# 0.net
KiCad netlist of a schematic drawn in Altium Designer
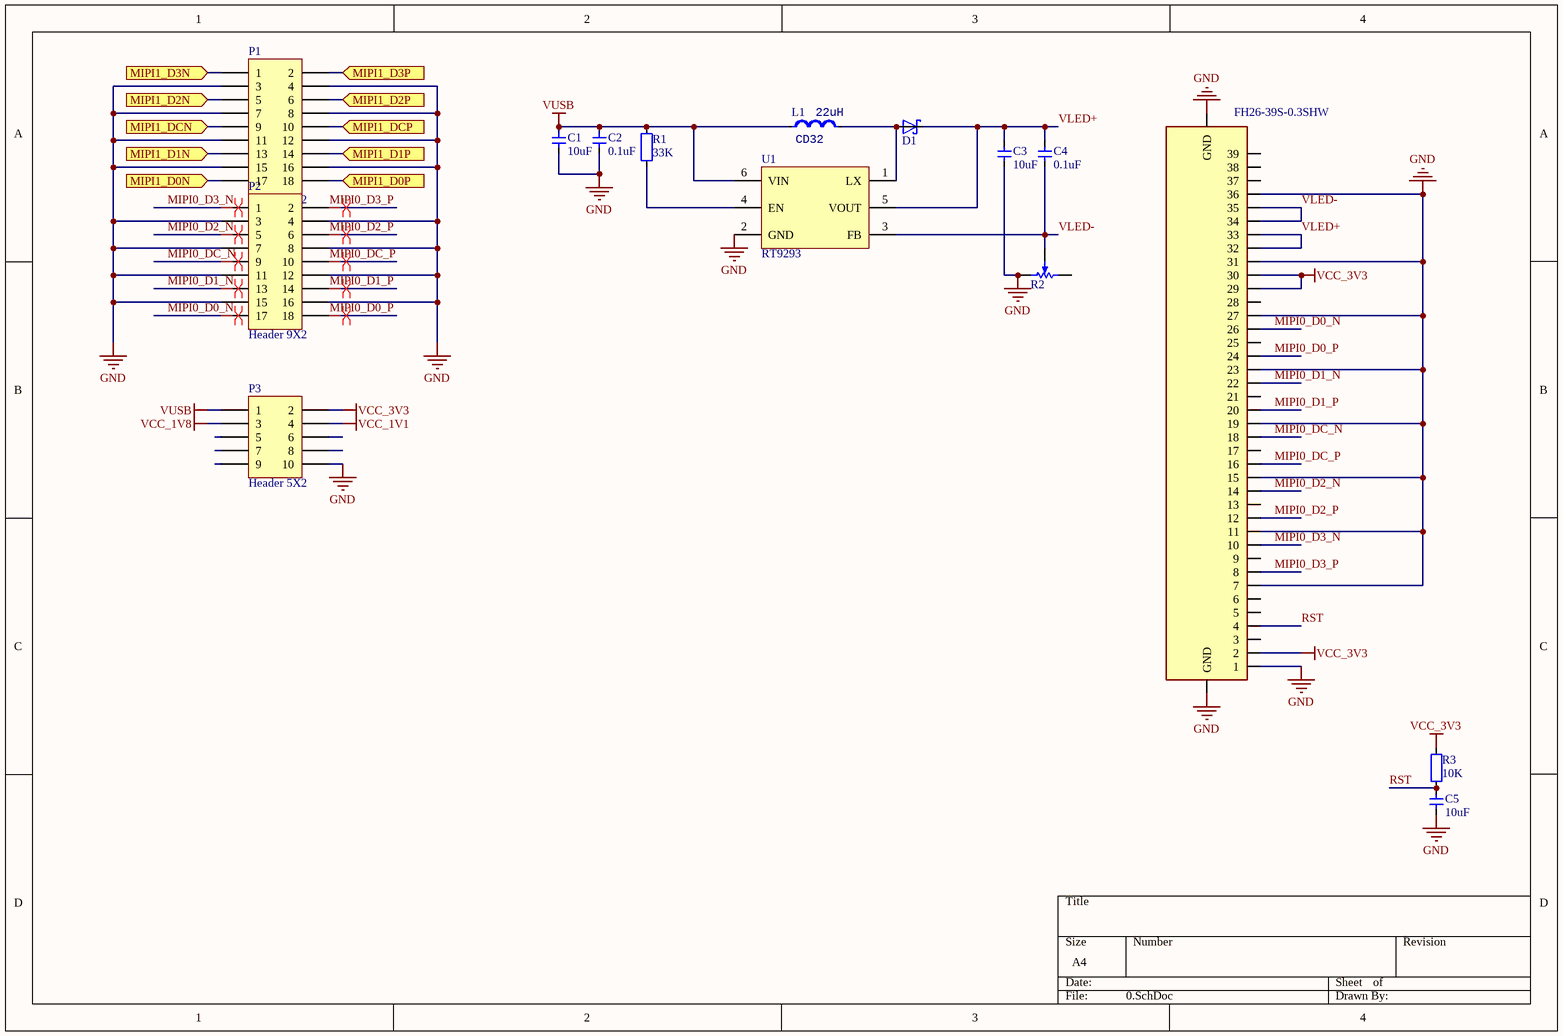
[diagram p0: 0.SchDoc]

(export (version "E")
  (design (tool "Eeschema 10.0.6"))
  (components
    (comp (ref "1")
      (value "FH26-39S-0.3SHW")
      (footprint "FH26-39S-0.3SHW")
      (description "39 Position FPC Connector Contacts, Bottom 0.012 _0.30mm_ Surface Mount, Right Angle")
      (fields (field (name "MF") "Hirose"))
      (libsource (lib "mLib") (part "FH26-39S-0.3SHW"))
    )
    (comp (ref "C1")
      (value "10uF")
      (footprint "0603_CAP")
      (description "Capacitor")
      (libsource (lib "MyPcbLib") (part "电容-0402"))
    )
    (comp (ref "C2")
      (value "0.1uF")
      (footprint "0603_CAP")
      (description "Capacitor")
      (libsource (lib "MyPcbLib") (part "电容-0402"))
    )
    (comp (ref "C3")
      (value "10uF")
      (footprint "0603_CAP")
      (description "Capacitor")
      (libsource (lib "MyPcbLib") (part "电容-0402"))
    )
    (comp (ref "C4")
      (value "0.1uF")
      (footprint "0603_CAP")
      (description "Capacitor")
      (libsource (lib "MyPcbLib") (part "电容-0402"))
    )
    (comp (ref "C5")
      (value "10uF")
      (footprint "0603_CAP")
      (description "Capacitor")
      (libsource (lib "MyPcbLib") (part "电容-0402"))
    )
    (comp (ref "D1")
      (value "RSX501L-20")
      (footprint "SOD-123F_L2.8-W1.8-LS3.7-RD")
      (description "Diode Schottky 40V 1A Surface Mount SMA _DO-214AC_")
      (fields (field (name "MP") "SS14") (field (name "MF") "ON Semiconductor"))
      (libsource (lib "mLib") (part "RSX501L-20"))
    )
    (comp (ref "L1")
      (value "22uH")
      (footprint "IND_CD32")
      (description "Inductor")
      (fields (field (name "TYPE") "CD32") (field (name "Comment") "CD32"))
      (libsource (lib "KitSprout") (part "Ind_CD32"))
    )
    (comp (ref "P1")
      (value "Header 9X2")
      (footprint "HDR2X9")
      (description "Header, 9-Pin, Dual row")
      (fields (field (name "PUBLISHER") "Altium Limited"))
      (libsource (lib "Miscellaneous Connectors") (part "Header 9X2"))
    )
    (comp (ref "P2")
      (value "Header 9X2")
      (footprint "HDR2X9")
      (description "Header, 9-Pin, Dual row")
      (fields (field (name "PUBLISHER") "Altium Limited"))
      (libsource (lib "Miscellaneous Connectors") (part "Header 9X2"))
    )
    (comp (ref "P3")
      (value "Header 5X2")
      (footprint "HDR2X5")
      (description "Header, 5-Pin, Dual row")
      (fields (field (name "PUBLISHER") "Altium Limited"))
      (libsource (lib "Miscellaneous Connectors") (part "Header 5X2"))
    )
    (comp (ref "R1")
      (value "33K")
      (footprint "0603_RES")
      (description "Resistor")
      (libsource (lib "MyPcbLib") (part "电阻-0402"))
    )
    (comp (ref "R2")
      (value "电位器-贴片")
      (footprint "贴片电位器 3*3")
      (fields (field (name "PUBLISHER") "Altium Limited"))
      (libsource (lib "MyPcbLib") (part "电位器-贴片"))
    )
    (comp (ref "R3")
      (value "10K")
      (footprint "0603_RES")
      (description "Resistor")
      (libsource (lib "MyPcbLib") (part "电阻-0402"))
    )
    (comp (ref "U1")
      (value "RT9293")
      (footprint "SOT23-6")
      (description "LCD-LED Driver")
      (libsource (lib "mLib") (part "RT9293"))
    )
  )
  (nets
    (net (code "1") (name "/MIPI0_D0_N") (class "Default")
      (node (ref "1") (pin "26") (pinfunction "26_26") (pintype "bidirectional"))
      (node (ref "P2") (pin "17") (pinfunction "17_17") (pintype "passive"))
    )
    (net (code "2") (name "/MIPI0_D0_P") (class "Default")
      (node (ref "1") (pin "24") (pinfunction "24_24") (pintype "bidirectional"))
      (node (ref "P2") (pin "18") (pinfunction "18_18") (pintype "passive"))
    )
    (net (code "3") (name "/MIPI0_D1_N") (class "Default")
      (node (ref "1") (pin "22") (pinfunction "22_22") (pintype "bidirectional"))
      (node (ref "P2") (pin "13") (pinfunction "13_13") (pintype "passive"))
    )
    (net (code "4") (name "/MIPI0_D1_P") (class "Default")
      (node (ref "1") (pin "20") (pinfunction "20_20") (pintype "bidirectional"))
      (node (ref "P2") (pin "14") (pinfunction "14_14") (pintype "passive"))
    )
    (net (code "5") (name "/MIPI0_D2_N") (class "Default")
      (node (ref "1") (pin "14") (pinfunction "14_14") (pintype "bidirectional"))
      (node (ref "P2") (pin "5") (pinfunction "5_5") (pintype "passive"))
    )
    (net (code "6") (name "/MIPI0_D2_P") (class "Default")
      (node (ref "1") (pin "12") (pinfunction "12_12") (pintype "bidirectional"))
      (node (ref "P2") (pin "6") (pinfunction "6_6") (pintype "passive"))
    )
    (net (code "7") (name "/MIPI0_D3_N") (class "Default")
      (node (ref "1") (pin "10") (pinfunction "10_10") (pintype "bidirectional"))
      (node (ref "P2") (pin "1") (pinfunction "1_1") (pintype "passive"))
    )
    (net (code "8") (name "/MIPI0_D3_P") (class "Default")
      (node (ref "1") (pin "8") (pinfunction "8_8") (pintype "bidirectional"))
      (node (ref "P2") (pin "2") (pinfunction "2_2") (pintype "passive"))
    )
    (net (code "9") (name "/MIPI0_DC_N") (class "Default")
      (node (ref "1") (pin "18") (pinfunction "18_18") (pintype "bidirectional"))
      (node (ref "P2") (pin "9") (pinfunction "9_9") (pintype "passive"))
    )
    (net (code "10") (name "/MIPI0_DC_P") (class "Default")
      (node (ref "1") (pin "16") (pinfunction "16_16") (pintype "bidirectional"))
      (node (ref "P2") (pin "10") (pinfunction "10_10") (pintype "passive"))
    )
    (net (code "11") (name "/MIPI1_D0N") (class "Default")
      (node (ref "P1") (pin "17") (pinfunction "17_17") (pintype "passive"))
    )
    (net (code "12") (name "/MIPI1_D0P") (class "Default")
      (node (ref "P1") (pin "18") (pinfunction "18_18") (pintype "passive"))
    )
    (net (code "13") (name "/MIPI1_D1N") (class "Default")
      (node (ref "P1") (pin "13") (pinfunction "13_13") (pintype "passive"))
    )
    (net (code "14") (name "/MIPI1_D1P") (class "Default")
      (node (ref "P1") (pin "14") (pinfunction "14_14") (pintype "passive"))
    )
    (net (code "15") (name "/MIPI1_D2N") (class "Default")
      (node (ref "P1") (pin "5") (pinfunction "5_5") (pintype "passive"))
    )
    (net (code "16") (name "/MIPI1_D2P") (class "Default")
      (node (ref "P1") (pin "6") (pinfunction "6_6") (pintype "passive"))
    )
    (net (code "17") (name "/MIPI1_D3N") (class "Default")
      (node (ref "P1") (pin "1") (pinfunction "1_1") (pintype "passive"))
    )
    (net (code "18") (name "/MIPI1_D3P") (class "Default")
      (node (ref "P1") (pin "2") (pinfunction "2_2") (pintype "passive"))
    )
    (net (code "19") (name "/MIPI1_DCN") (class "Default")
      (node (ref "P1") (pin "9") (pinfunction "9_9") (pintype "passive"))
    )
    (net (code "20") (name "/MIPI1_DCP") (class "Default")
      (node (ref "P1") (pin "10") (pinfunction "10_10") (pintype "passive"))
    )
    (net (code "21") (name "/RST") (class "Default")
      (node (ref "1") (pin "4") (pinfunction "4_4") (pintype "bidirectional"))
      (node (ref "C5") (pin "2") (pinfunction "2_2") (pintype "passive"))
      (node (ref "R3") (pin "1") (pinfunction "1_1") (pintype "passive"))
    )
    (net (code "22") (name "/VLED+") (class "Default")
      (node (ref "1") (pin "32") (pinfunction "32_32") (pintype "bidirectional"))
      (node (ref "1") (pin "33") (pinfunction "33_33") (pintype "bidirectional"))
      (node (ref "C3") (pin "2") (pinfunction "2_2") (pintype "passive"))
      (node (ref "C4") (pin "2") (pinfunction "2_2") (pintype "passive"))
      (node (ref "D1") (pin "1") (pinfunction "1_1") (pintype "passive"))
      (node (ref "U1") (pin "5") (pinfunction "VOUT_5") (pintype "passive"))
    )
    (net (code "23") (name "/VLED-") (class "Default")
      (node (ref "1") (pin "34") (pinfunction "34_34") (pintype "bidirectional"))
      (node (ref "1") (pin "35") (pinfunction "35_35") (pintype "bidirectional"))
      (node (ref "C4") (pin "1") (pinfunction "1_1") (pintype "passive"))
      (node (ref "R2") (pin "3") (pinfunction "W_3") (pintype "passive"))
      (node (ref "U1") (pin "3") (pinfunction "FB_3") (pintype "passive"))
    )
    (net (code "24") (name "GND") (class "Default")
      (node (ref "1") (pin "1") (pinfunction "1_1") (pintype "bidirectional"))
      (node (ref "1") (pin "11") (pinfunction "11_11") (pintype "bidirectional"))
      (node (ref "1") (pin "15") (pinfunction "15_15") (pintype "bidirectional"))
      (node (ref "1") (pin "19") (pinfunction "19_19") (pintype "bidirectional"))
      (node (ref "1") (pin "23") (pinfunction "23_23") (pintype "bidirectional"))
      (node (ref "1") (pin "27") (pinfunction "27_27") (pintype "bidirectional"))
      (node (ref "1") (pin "31") (pinfunction "31_31") (pintype "bidirectional"))
      (node (ref "1") (pin "36") (pinfunction "36_36") (pintype "bidirectional"))
      (node (ref "1") (pin "7") (pinfunction "7_7") (pintype "bidirectional"))
      (node (ref "1") (pin "GND1") (pinfunction "GND_GND1") (pintype "power_in"))
      (node (ref "1") (pin "GND2") (pinfunction "GND_GND2") (pintype "power_in"))
      (node (ref "C1") (pin "1") (pinfunction "1_1") (pintype "passive"))
      (node (ref "C2") (pin "1") (pinfunction "1_1") (pintype "passive"))
      (node (ref "C3") (pin "1") (pinfunction "1_1") (pintype "passive"))
      (node (ref "C5") (pin "1") (pinfunction "1_1") (pintype "passive"))
      (node (ref "P1") (pin "11") (pinfunction "11_11") (pintype "passive"))
      (node (ref "P1") (pin "12") (pinfunction "12_12") (pintype "passive"))
      (node (ref "P1") (pin "15") (pinfunction "15_15") (pintype "passive"))
      (node (ref "P1") (pin "16") (pinfunction "16_16") (pintype "passive"))
      (node (ref "P1") (pin "3") (pinfunction "3_3") (pintype "passive"))
      (node (ref "P1") (pin "4") (pinfunction "4_4") (pintype "passive"))
      (node (ref "P1") (pin "7") (pinfunction "7_7") (pintype "passive"))
      (node (ref "P1") (pin "8") (pinfunction "8_8") (pintype "passive"))
      (node (ref "P2") (pin "11") (pinfunction "11_11") (pintype "passive"))
      (node (ref "P2") (pin "12") (pinfunction "12_12") (pintype "passive"))
      (node (ref "P2") (pin "15") (pinfunction "15_15") (pintype "passive"))
      (node (ref "P2") (pin "16") (pinfunction "16_16") (pintype "passive"))
      (node (ref "P2") (pin "3") (pinfunction "3_3") (pintype "passive"))
      (node (ref "P2") (pin "4") (pinfunction "4_4") (pintype "passive"))
      (node (ref "P2") (pin "7") (pinfunction "7_7") (pintype "passive"))
      (node (ref "P2") (pin "8") (pinfunction "8_8") (pintype "passive"))
      (node (ref "P3") (pin "10") (pinfunction "10_10") (pintype "passive"))
      (node (ref "R2") (pin "1") (pinfunction "+_1") (pintype "passive"))
      (node (ref "U1") (pin "2") (pinfunction "GND_2") (pintype "passive"))
    )
    (net (code "25") (name "Net-(U1-EN)") (class "Default")
      (node (ref "R1") (pin "1") (pinfunction "1_1") (pintype "passive"))
      (node (ref "U1") (pin "4") (pinfunction "EN_4") (pintype "passive"))
    )
    (net (code "26") (name "Net-(U1-LX)") (class "Default")
      (node (ref "D1") (pin "2") (pinfunction "2_2") (pintype "passive"))
      (node (ref "L1") (pin "2") (pinfunction "2_2") (pintype "passive"))
      (node (ref "U1") (pin "1") (pinfunction "LX_1") (pintype "passive"))
    )
    (net (code "27") (name "VCC_1V1") (class "Default")
      (node (ref "P3") (pin "4") (pinfunction "4_4") (pintype "passive"))
    )
    (net (code "28") (name "VCC_1V8") (class "Default")
      (node (ref "P3") (pin "3") (pinfunction "3_3") (pintype "passive"))
    )
    (net (code "29") (name "VCC_3V3") (class "Default")
      (node (ref "1") (pin "2") (pinfunction "2_2") (pintype "bidirectional"))
      (node (ref "1") (pin "29") (pinfunction "29_29") (pintype "bidirectional"))
      (node (ref "1") (pin "30") (pinfunction "30_30") (pintype "bidirectional"))
      (node (ref "P3") (pin "2") (pinfunction "2_2") (pintype "passive"))
      (node (ref "R3") (pin "2") (pinfunction "2_2") (pintype "passive"))
    )
    (net (code "30") (name "VUSB") (class "Default")
      (node (ref "C1") (pin "2") (pinfunction "2_2") (pintype "passive"))
      (node (ref "C2") (pin "2") (pinfunction "2_2") (pintype "passive"))
      (node (ref "L1") (pin "1") (pinfunction "1_1") (pintype "passive"))
      (node (ref "P3") (pin "1") (pinfunction "1_1") (pintype "passive"))
      (node (ref "R1") (pin "2") (pinfunction "2_2") (pintype "passive"))
      (node (ref "U1") (pin "6") (pinfunction "VIN_6") (pintype "passive"))
    )
    (net (code "31") (name "unconnected-(1-Pad3)") (class "Default")
      (node (ref "1") (pin "3") (pinfunction "3_3") (pintype "bidirectional"))
    )
    (net (code "32") (name "unconnected-(1-Pad5)") (class "Default")
      (node (ref "1") (pin "5") (pinfunction "5_5") (pintype "bidirectional"))
    )
    (net (code "33") (name "unconnected-(1-Pad6)") (class "Default")
      (node (ref "1") (pin "6") (pinfunction "6_6") (pintype "bidirectional"))
    )
    (net (code "34") (name "unconnected-(1-Pad9)") (class "Default")
      (node (ref "1") (pin "9") (pinfunction "9_9") (pintype "bidirectional"))
    )
    (net (code "35") (name "unconnected-(1-Pad13)") (class "Default")
      (node (ref "1") (pin "13") (pinfunction "13_13") (pintype "bidirectional"))
    )
    (net (code "36") (name "unconnected-(1-Pad17)") (class "Default")
      (node (ref "1") (pin "17") (pinfunction "17_17") (pintype "bidirectional"))
    )
    (net (code "37") (name "unconnected-(1-Pad21)") (class "Default")
      (node (ref "1") (pin "21") (pinfunction "21_21") (pintype "bidirectional"))
    )
    (net (code "38") (name "unconnected-(1-Pad25)") (class "Default")
      (node (ref "1") (pin "25") (pinfunction "25_25") (pintype "bidirectional"))
    )
    (net (code "39") (name "unconnected-(1-Pad28)") (class "Default")
      (node (ref "1") (pin "28") (pinfunction "28_28") (pintype "bidirectional"))
    )
    (net (code "40") (name "unconnected-(1-Pad37)") (class "Default")
      (node (ref "1") (pin "37") (pinfunction "37_37") (pintype "bidirectional"))
    )
    (net (code "41") (name "unconnected-(1-Pad38)") (class "Default")
      (node (ref "1") (pin "38") (pinfunction "38_38") (pintype "bidirectional"))
    )
    (net (code "42") (name "unconnected-(1-Pad39)") (class "Default")
      (node (ref "1") (pin "39") (pinfunction "39_39") (pintype "bidirectional"))
    )
    (net (code "43") (name "unconnected-(P3-Pad5)") (class "Default")
      (node (ref "P3") (pin "5") (pinfunction "5_5") (pintype "passive"))
    )
    (net (code "44") (name "unconnected-(P3-Pad6)") (class "Default")
      (node (ref "P3") (pin "6") (pinfunction "6_6") (pintype "passive"))
    )
    (net (code "45") (name "unconnected-(P3-Pad7)") (class "Default")
      (node (ref "P3") (pin "7") (pinfunction "7_7") (pintype "passive"))
    )
    (net (code "46") (name "unconnected-(P3-Pad8)") (class "Default")
      (node (ref "P3") (pin "8") (pinfunction "8_8") (pintype "passive"))
    )
    (net (code "47") (name "unconnected-(P3-Pad9)") (class "Default")
      (node (ref "P3") (pin "9") (pinfunction "9_9") (pintype "passive"))
    )
    (net (code "48") (name "unconnected-(R2---Pad2)") (class "Default")
      (node (ref "R2") (pin "2") (pinfunction "-_2") (pintype "passive"))
    )
  )
)
